# Rcrd_Brkr.net
KiCad netlist of a schematic drawn in Altium Designer
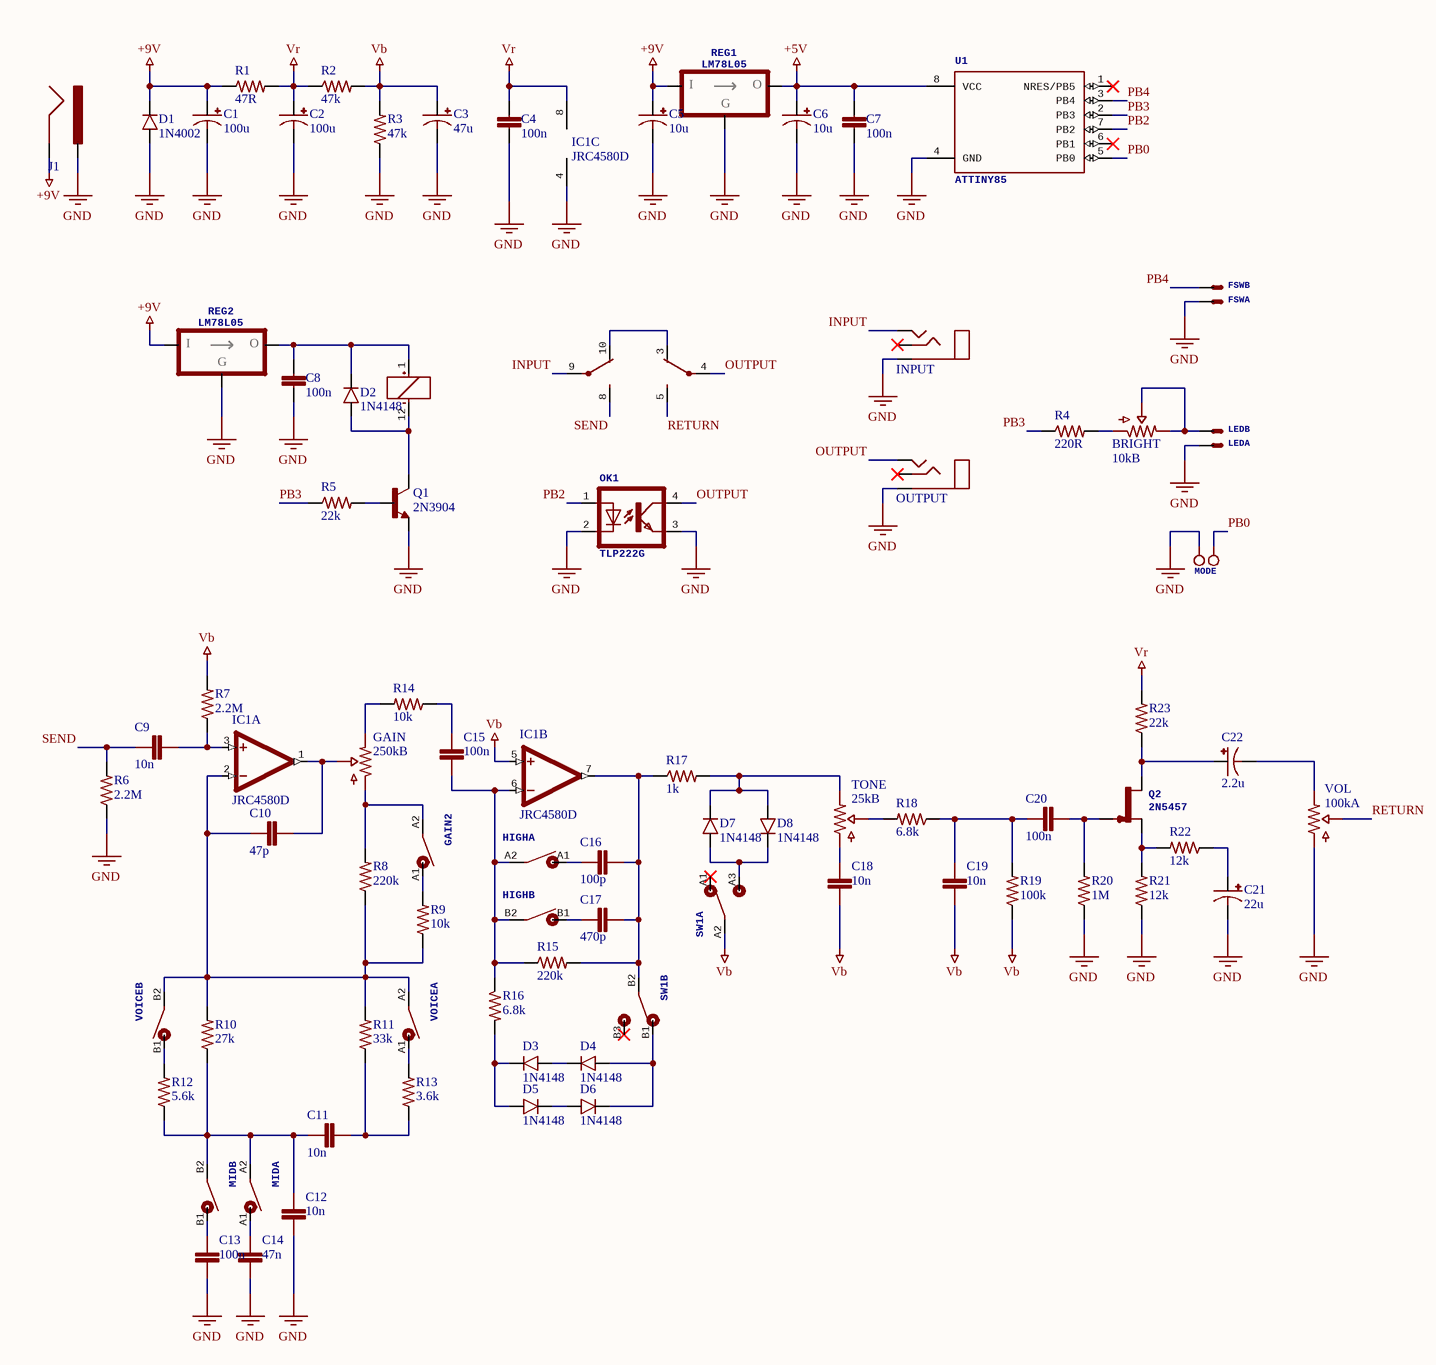
[diagram p0: Rcrd Brkr.SchDoc]

(export (version "E")
  (design (tool "Eeschema 10.0.6"))
  (components
    (comp (ref "BRIGHT")
      (value "10kB")
      (footprint "BOURNS_3362P")
      (description "10k Lin 3362P trimmer")
      (libsource (lib "Pedals") (part "TRIM_10kB_3362P"))
    )
    (comp (ref "C1")
      (value "100u")
      (footprint "ELEC_050_020")
      (description "100u 16V electrolytic capacitor")
      (libsource (lib "Pedals") (part "C_ELEC_100u_16V"))
    )
    (comp (ref "C2")
      (value "100u")
      (footprint "ELEC_050_020")
      (description "100u 16V electrolytic capacitor")
      (libsource (lib "Pedals") (part "C_ELEC_100u_16V"))
    )
    (comp (ref "C3")
      (value "47u")
      (footprint "ELEC_050_020")
      (description "47u 25V electrolytic capacitor")
      (libsource (lib "Pedals") (part "ELEC_47u_25V"))
    )
    (comp (ref "C4")
      (value "100n")
      (footprint "CER_050")
      (description "100n MLCC X7R radial capacitor")
      (libsource (lib "") (part "CER_100n_1"))
    )
    (comp (ref "C5")
      (value "10u")
      (footprint "ELEC_040_020")
      (description "10u 50V electrolytic capacitor")
      (libsource (lib "Pedals") (part "ELEC_10u_50V"))
    )
    (comp (ref "C6")
      (value "10u")
      (footprint "ELEC_040_020")
      (description "10u 50V electrolytic capacitor")
      (libsource (lib "Pedals") (part "ELEC_10u_50V"))
    )
    (comp (ref "C7")
      (value "100n")
      (footprint "CER_050")
      (description "100n MLCC X7R radial capacitor")
      (libsource (lib "Pedals") (part "CER_100n"))
    )
    (comp (ref "C8")
      (value "100n")
      (footprint "CER_050")
      (description "100n MLCC X7R radial capacitor")
      (libsource (lib "") (part "CER_100n_1"))
    )
    (comp (ref "C9")
      (value "10n")
      (footprint "FILMBOX_SMALL")
      (description "10n 100V polyester film box capacitor")
      (libsource (lib "") (part "FILMBOX_10n_2"))
    )
    (comp (ref "C10")
      (value "47p")
      (footprint "CER_050")
      (description "47p MLCC X7R radial capacitor")
      (libsource (lib "Pedals") (part "C_CER_47p"))
    )
    (comp (ref "C11")
      (value "10n")
      (footprint "FILMBOX_SMALL")
      (description "10n 100V polyester film box capacitor")
      (libsource (lib "") (part "FILMBOX_10n_2"))
    )
    (comp (ref "C12")
      (value "10n")
      (footprint "FILMBOX_SMALL")
      (description "10n 100V polyester film box capacitor")
      (libsource (lib "Pedals") (part "FILMBOX_10n"))
    )
    (comp (ref "C13")
      (value "100n")
      (footprint "FILMBOX_SMALL")
      (description "100n 100V polyester film box capacitor")
      (libsource (lib "") (part "C_FILMBOX_100n_1"))
    )
    (comp (ref "C14")
      (value "47n")
      (footprint "FILMBOX_SMALL")
      (description "47n 100V polyester film box capacitor")
      (libsource (lib "Pedals") (part "C_FILMBOX_47n"))
    )
    (comp (ref "C15")
      (value "100n")
      (footprint "FILMBOX_SMALL")
      (description "100n 100V polyester film box capacitor")
      (libsource (lib "Pedals") (part "FILMBOX_100n"))
    )
    (comp (ref "C16")
      (value "100p")
      (footprint "CER_050")
      (description "100p MLCC X7R radial capacitor")
      (libsource (lib "Pedals") (part "C_CER_100p"))
    )
    (comp (ref "C17")
      (value "470p")
      (footprint "CER_050")
      (description "470p MLCC X7R radial capacitor")
      (libsource (lib "Pedals") (part "C_CER_470p"))
    )
    (comp (ref "C18")
      (value "10n")
      (footprint "FILMBOX_SMALL")
      (description "10n 100V polyester film box capacitor")
      (libsource (lib "Pedals") (part "FILMBOX_10n"))
    )
    (comp (ref "C19")
      (value "10n")
      (footprint "FILMBOX_SMALL")
      (description "10n 100V polyester film box capacitor")
      (libsource (lib "") (part "FILMBOX_10n_1"))
    )
    (comp (ref "C20")
      (value "100n")
      (footprint "FILMBOX_SMALL")
      (description "100n 100V polyester film box capacitor")
      (libsource (lib "Pedals") (part "C_FILMBOX_100n"))
    )
    (comp (ref "C21")
      (value "22u")
      (footprint "ELEC_LESR_050_020")
      (description "22u 50V Low ESR ectrolytic capacitor")
      (libsource (lib "Pedals") (part "C_ELEC_LESR_22u_50V"))
    )
    (comp (ref "C22")
      (value "2.2u")
      (footprint "ELEC_LESR_050_020")
      (description "2.2u 50V Low ESR ectrolytic capacitor")
      (libsource (lib "Pedals") (part "C_ELEC_LESR_2.2u_50V"))
    )
    (comp (ref "D1") (value "1N4002") (footprint "DO41_2") (libsource (lib "Pedals") (part "1N4002")))
    (comp (ref "D2") (value "1N4148") (footprint "DO35_2") (libsource (lib "Pedals") (part "1N4148")))
    (comp (ref "D3") (value "1N4148") (footprint "DO35_2") (libsource (lib "Pedals") (part "1N4148")))
    (comp (ref "D4") (value "1N4148") (footprint "DO35_2") (libsource (lib "Pedals") (part "1N4148")))
    (comp (ref "D5") (value "1N4148") (footprint "DO35_2") (libsource (lib "Pedals") (part "1N4148")))
    (comp (ref "D6") (value "1N4148") (footprint "DO35_2") (libsource (lib "Pedals") (part "1N4148")))
    (comp (ref "D7") (value "1N4148") (footprint "DO35_2") (libsource (lib "Pedals") (part "1N4148")))
    (comp (ref "D8") (value "1N4148") (footprint "DO35_2") (libsource (lib "Pedals") (part "1N4148")))
    (comp (ref "FSW")
      (value "~")
      (footprint "JST-XH-02")
      (description "2 Pins male XH header")
      (libsource (lib "Pedals") (part "JST-XH-02"))
    )
    (comp (ref "GAIN")
      (value "250kB")
      (footprint "ALPHA_16mm_BOTTOM")
      (description "250k Lin potentiometer round shaft")
      (libsource (lib "Pedals") (part "250kB_ALPHA_16mm"))
    )
    (comp (ref "GAIN2")
      (value "DIP")
      (footprint "DIP_1WAY")
      (description "DIP Switch 1 way")
      (libsource (lib "Pedals") (part "SW_DIP_1WAY"))
    )
    (comp (ref "HIGH")
      (value "DIP")
      (footprint "DIP_2WAY")
      (description "DIP Switch 2 way")
      (libsource (lib "Pedals") (part "SW_DIP_2WAY"))
    )
    (comp (ref "IC1") (value "JRC4580D") (footprint "DIL8") (libsource (lib "Pedals") (part "JRC4580D")))
    (comp (ref "INPUT")
      (value "~")
      (footprint "STEREO")
      (description "6.35mm stereo insulated socket jack PCB mounted")
      (libsource (lib "Pedals") (part "STEREO"))
    )
    (comp (ref "J1")
      (value "DC_JACK")
      (footprint "DC_JACK")
      (description "DC Power jack 2.1mm barrel")
      (libsource (lib "Pedals") (part "DC_JACK"))
    )
    (comp (ref "K1")
      (value "~")
      (footprint "NA5")
      (description "NA5W-K")
      (libsource (lib "") (part "NA5W-K_1"))
    )
    (comp (ref "LED")
      (value "~")
      (footprint "JST-XH-02")
      (description "2 Pins male XH header")
      (libsource (lib "Pedals") (part "JST-XH-02"))
    )
    (comp (ref "MID")
      (value "DIP")
      (footprint "DIP_2WAY")
      (description "DIP Switch 2 way")
      (libsource (lib "Pedals") (part "SW_DIP_2WAY"))
    )
    (comp (ref "MODE")
      (value "HEADER_2PINS")
      (footprint "HEADER_2PINS")
      (description "2 Pins male header")
      (libsource (lib "Pedals") (part "HEADER_2PINS"))
    )
    (comp (ref "OK1") (value "TLP222G") (footprint "DIL4") (libsource (lib "Pedals") (part "TLP222G")))
    (comp (ref "OUTPUT")
      (value "~")
      (footprint "STEREO")
      (description "6.35mm stereo insulated socket jack PCB mounted")
      (libsource (lib "Pedals") (part "STEREO"))
    )
    (comp (ref "Q1") (value "2N3904") (footprint "TO92") (libsource (lib "Pedals") (part "2N3904")))
    (comp (ref "Q2") (value "2N5457") (footprint "TO92") (libsource (lib "Pedals") (part "Q_2N5457")))
    (comp (ref "R1")
      (value "47R")
      (footprint "R_3_47R_025W")
      (description "47R metal film 1/4W Resistor")
      (libsource (lib "Pedals") (part "R_3_47R_025W"))
    )
    (comp (ref "R2")
      (value "47k")
      (footprint "R_3_47k_025W")
      (description "47k metal film 1/4W Resistor")
      (libsource (lib "Pedals") (part "R_3_47k_025W"))
    )
    (comp (ref "R3")
      (value "47k")
      (footprint "R_3_47k_025W")
      (description "47k metal film 1/4W Resistor")
      (libsource (lib "Pedals") (part "R_3_47k_025W"))
    )
    (comp (ref "R4")
      (value "220R")
      (footprint "R_3_220R_025W")
      (description "220R metal film 1/4W Resistor")
      (libsource (lib "Pedals") (part "R_3_220R_025W"))
    )
    (comp (ref "R5")
      (value "22k")
      (footprint "R_3_22k_025W")
      (description "22k metal film 1/4W Resistor")
      (libsource (lib "Pedals") (part "R_3_22k_025W"))
    )
    (comp (ref "R6")
      (value "2.2M")
      (footprint "R_3_2,2M_025W")
      (description "2.2M metal film 1/4W Resistor")
      (libsource (lib "Pedals") (part "R_3_2.2M_025W"))
    )
    (comp (ref "R7")
      (value "2.2M")
      (footprint "R_3_2,2M_025W")
      (description "2.2M metal film 1/4W Resistor")
      (libsource (lib "Pedals") (part "R_3_2.2M_025W"))
    )
    (comp (ref "R8")
      (value "220k")
      (footprint "R_3_220k_025W")
      (description "220k metal film 1/4W Resistor")
      (libsource (lib "Pedals") (part "R_3_220k_025W"))
    )
    (comp (ref "R9")
      (value "10k")
      (footprint "R_3_10k_025W")
      (description "10k metal film 1/4W Resistor")
      (libsource (lib "Pedals") (part "R_3_10k_025W"))
    )
    (comp (ref "R10")
      (value "27k")
      (footprint "R_3_27k_025W")
      (description "27k metal film 1/4W Resistor")
      (libsource (lib "Pedals") (part "R_3_27k_025W"))
    )
    (comp (ref "R11")
      (value "33k")
      (footprint "R_3_33k_025W")
      (description "33k metal film 1/4W Resistor")
      (libsource (lib "Pedals") (part "R_3_33k_025W"))
    )
    (comp (ref "R12")
      (value "5.6k")
      (footprint "R_3_5.6k_025W")
      (description "5.6k metal film 1/4W Resistor")
      (libsource (lib "Pedals") (part "R_3_5.6k_025W"))
    )
    (comp (ref "R13")
      (value "3.6k")
      (footprint "R_3_3.6k_025W")
      (description "3.6k metal film 1/4W Resistor")
      (libsource (lib "Pedals") (part "R_3_3.6k_025W"))
    )
    (comp (ref "R14")
      (value "10k")
      (footprint "R_3_10k_025W")
      (description "10k metal film 1/4W Resistor")
      (libsource (lib "Pedals") (part "R_3_10k_025W"))
    )
    (comp (ref "R15")
      (value "220k")
      (footprint "R_3_220k_025W")
      (description "220k metal film 1/4W Resistor")
      (libsource (lib "Pedals") (part "R_3_220k_025W"))
    )
    (comp (ref "R16")
      (value "6.8k")
      (footprint "R_3_6.8k_025W")
      (description "6.8k metal film 1/4W Resistor")
      (libsource (lib "Pedals") (part "R_3_6.8k_025W"))
    )
    (comp (ref "R17")
      (value "1k")
      (footprint "R_3_1k_025W")
      (description "1k metal film 1/4W Resistor")
      (libsource (lib "Pedals") (part "R_3_1k_025W"))
    )
    (comp (ref "R18")
      (value "6.8k")
      (footprint "R_3_6.8k_025W")
      (description "6.8k metal film 1/4W Resistor")
      (libsource (lib "Pedals") (part "R_3_6.8k_025W"))
    )
    (comp (ref "R19")
      (value "100k")
      (footprint "R_3_100k_025W")
      (description "100k metal film 1/4W Resistor")
      (libsource (lib "Pedals") (part "R_3_100k_025W"))
    )
    (comp (ref "R20")
      (value "1M")
      (footprint "R_3_1M_025W")
      (description "1M metal film 1/4W Resistor")
      (libsource (lib "Pedals") (part "R_3_1M_025W"))
    )
    (comp (ref "R21")
      (value "12k")
      (footprint "R_3_12k_025W")
      (description "12k metal film 1/4W Resistor")
      (libsource (lib "Pedals") (part "R_3_12k_025W"))
    )
    (comp (ref "R22")
      (value "12k")
      (footprint "R_3_12k_025W")
      (description "12k metal film 1/4W Resistor")
      (libsource (lib "Pedals") (part "R_3_12k_025W"))
    )
    (comp (ref "R23")
      (value "22k")
      (footprint "R_3_22k_025W")
      (description "22k metal film 1/4W Resistor")
      (libsource (lib "Pedals") (part "R_3_22k_025W"))
    )
    (comp (ref "REG1")
      (value "LM78L05")
      (footprint "TO92")
      (description "78L05")
      (libsource (lib "Pedals") (part "LM78L05"))
    )
    (comp (ref "REG2")
      (value "LM78L05")
      (footprint "TO92")
      (description "78L05")
      (libsource (lib "Pedals") (part "LM78L05"))
    )
    (comp (ref "SW1")
      (value "DPDT")
      (footprint "DPDT")
      (description "DPDT toggle switch ON/OFF/ON")
      (libsource (lib "") (part "DPDT_ON-OFF-ON_1"))
    )
    (comp (ref "TONE")
      (value "25kB")
      (footprint "ALPHA_16mm_BOTTOM")
      (description "25k Lin potentiometer round shaft")
      (libsource (lib "Pedals") (part "25kB_ALPHA_16mm"))
    )
    (comp (ref "U1")
      (value "ATTINY85")
      (footprint "DIP8")
      (description "ATTINY85-20PU")
      (libsource (lib "Pedals") (part "ATTINY85"))
    )
    (comp (ref "VOICE")
      (value "DIP")
      (footprint "DIP_2WAY")
      (description "DIP Switch 2 way")
      (libsource (lib "") (part "SW_DIP_2WAY_2"))
    )
    (comp (ref "VOL")
      (value "100kA")
      (footprint "ALPHA_16mm_BOTTOM")
      (description "100k Log potentiometer round shaft")
      (libsource (lib "Pedals") (part "100kA_ALPHA_16mm"))
    )
  )
  (nets
    (net (code "1") (name "+5V") (class "Default")
      (node (ref "C6") (pin "+") (pinfunction "+_+") (pintype "passive"))
      (node (ref "C7") (pin "2") (pinfunction "2_2") (pintype "passive"))
      (node (ref "REG1") (pin "3") (pinfunction "VO_3") (pintype "power_in"))
      (node (ref "U1") (pin "8") (pinfunction "VCC_8") (pintype "power_in"))
    )
    (net (code "2") (name "+9V") (class "Default")
      (node (ref "C1") (pin "+") (pinfunction "+_+") (pintype "passive"))
      (node (ref "C5") (pin "+") (pinfunction "+_+") (pintype "passive"))
      (node (ref "D1") (pin "C") (pinfunction "C_C") (pintype "passive"))
      (node (ref "J1") (pin "GND") (pinfunction "GND_GND") (pintype "passive"))
      (node (ref "R1") (pin "1") (pinfunction "1_1") (pintype "passive"))
      (node (ref "REG1") (pin "1") (pinfunction "VI_1") (pintype "power_in"))
      (node (ref "REG2") (pin "1") (pinfunction "VI_1") (pintype "power_in"))
    )
    (net (code "3") (name "/INPUT") (class "Default")
      (node (ref "INPUT") (pin "T") (pinfunction "T_T") (pintype "passive"))
      (node (ref "K1") (pin "9") (pinfunction "P_9") (pintype "passive"))
    )
    (net (code "4") (name "/OUTPUT") (class "Default")
      (node (ref "K1") (pin "4") (pinfunction "P_4") (pintype "passive"))
      (node (ref "OK1") (pin "4") (pinfunction "COL_4") (pintype "passive"))
      (node (ref "OUTPUT") (pin "T") (pinfunction "T_T") (pintype "passive"))
    )
    (net (code "5") (name "/PB0") (class "Default")
      (node (ref "MODE") (pin "2") (pinfunction "2_2") (pintype "passive"))
      (node (ref "U1") (pin "5") (pinfunction "PB0_5") (pintype "bidirectional"))
    )
    (net (code "6") (name "/PB2") (class "Default")
      (node (ref "OK1") (pin "1") (pinfunction "A_1") (pintype "passive"))
      (node (ref "U1") (pin "7") (pinfunction "PB2_7") (pintype "bidirectional"))
    )
    (net (code "7") (name "/PB3") (class "Default")
      (node (ref "R4") (pin "1") (pinfunction "1_1") (pintype "passive"))
      (node (ref "R5") (pin "1") (pinfunction "1_1") (pintype "passive"))
      (node (ref "U1") (pin "2") (pinfunction "PB3_2") (pintype "bidirectional"))
    )
    (net (code "8") (name "/PB4") (class "Default")
      (node (ref "FSW") (pin "1") (pinfunction "S_1") (pintype "passive"))
      (node (ref "U1") (pin "3") (pinfunction "PB4_3") (pintype "bidirectional"))
    )
    (net (code "9") (name "/RETURN") (class "Default")
      (node (ref "K1") (pin "5") (pinfunction "S_5") (pintype "passive"))
      (node (ref "VOL") (pin "2") (pinfunction "2_2") (pintype "passive"))
    )
    (net (code "10") (name "/SEND") (class "Default")
      (node (ref "C9") (pin "2") (pinfunction "2_2") (pintype "passive"))
      (node (ref "K1") (pin "8") (pinfunction "S_8") (pintype "passive"))
      (node (ref "R6") (pin "2") (pinfunction "2_2") (pintype "passive"))
    )
    (net (code "11") (name "GND") (class "Default")
      (node (ref "C1") (pin "-") (pinfunction "-_-") (pintype "passive"))
      (node (ref "C12") (pin "2") (pinfunction "2_2") (pintype "passive"))
      (node (ref "C13") (pin "2") (pinfunction "2_2") (pintype "passive"))
      (node (ref "C14") (pin "2") (pinfunction "2_2") (pintype "passive"))
      (node (ref "C2") (pin "-") (pinfunction "-_-") (pintype "passive"))
      (node (ref "C21") (pin "-") (pinfunction "-_-") (pintype "passive"))
      (node (ref "C3") (pin "-") (pinfunction "-_-") (pintype "passive"))
      (node (ref "C4") (pin "2") (pinfunction "2_2") (pintype "passive"))
      (node (ref "C5") (pin "-") (pinfunction "-_-") (pintype "passive"))
      (node (ref "C6") (pin "-") (pinfunction "-_-") (pintype "passive"))
      (node (ref "C7") (pin "1") (pinfunction "1_1") (pintype "passive"))
      (node (ref "C8") (pin "2") (pinfunction "2_2") (pintype "passive"))
      (node (ref "D1") (pin "A") (pinfunction "A_A") (pintype "passive"))
      (node (ref "FSW") (pin "2") (pinfunction "S_2") (pintype "passive"))
      (node (ref "IC1") (pin "4") (pinfunction "V-_4") (pintype "power_in"))
      (node (ref "INPUT") (pin "S") (pinfunction "S_S") (pintype "passive"))
      (node (ref "J1") (pin "PWR") (pinfunction "PWR_PWR") (pintype "passive"))
      (node (ref "LED") (pin "2") (pinfunction "S_2") (pintype "passive"))
      (node (ref "MODE") (pin "1") (pinfunction "1_1") (pintype "passive"))
      (node (ref "OK1") (pin "2") (pinfunction "C_2") (pintype "passive"))
      (node (ref "OK1") (pin "3") (pinfunction "EMIT_3") (pintype "passive"))
      (node (ref "OUTPUT") (pin "S") (pinfunction "S_S") (pintype "passive"))
      (node (ref "Q1") (pin "3") (pinfunction "E_3") (pintype "passive"))
      (node (ref "R20") (pin "1") (pinfunction "1_1") (pintype "passive"))
      (node (ref "R21") (pin "1") (pinfunction "1_1") (pintype "passive"))
      (node (ref "R3") (pin "1") (pinfunction "1_1") (pintype "passive"))
      (node (ref "R6") (pin "1") (pinfunction "1_1") (pintype "passive"))
      (node (ref "REG1") (pin "2") (pinfunction "GND_2") (pintype "power_in"))
      (node (ref "REG2") (pin "2") (pinfunction "GND_2") (pintype "power_in"))
      (node (ref "U1") (pin "4") (pinfunction "GND_4") (pintype "power_in"))
      (node (ref "VOL") (pin "1") (pinfunction "1_1") (pintype "passive"))
    )
    (net (code "12") (name "Net-(BRIGHT-Pad1)") (class "Default")
      (node (ref "BRIGHT") (pin "1") (pinfunction "1_1") (pintype "passive"))
      (node (ref "R4") (pin "2") (pinfunction "2_2") (pintype "passive"))
    )
    (net (code "13") (name "Net-(C11-Pad1)") (class "Default")
      (node (ref "C11") (pin "1") (pinfunction "1_1") (pintype "passive"))
      (node (ref "R11") (pin "1") (pinfunction "1_1") (pintype "passive"))
      (node (ref "R13") (pin "1") (pinfunction "1_1") (pintype "passive"))
    )
    (net (code "14") (name "Net-(C15-Pad1)") (class "Default")
      (node (ref "C15") (pin "1") (pinfunction "1_1") (pintype "passive"))
      (node (ref "R14") (pin "1") (pinfunction "1_1") (pintype "passive"))
    )
    (net (code "15") (name "Net-(C18-Pad1)") (class "Default")
      (node (ref "C18") (pin "1") (pinfunction "1_1") (pintype "passive"))
      (node (ref "TONE") (pin "1") (pinfunction "1_1") (pintype "passive"))
    )
    (net (code "16") (name "Net-(C19-Pad2)") (class "Default")
      (node (ref "C19") (pin "2") (pinfunction "2_2") (pintype "passive"))
      (node (ref "C20") (pin "2") (pinfunction "2_2") (pintype "passive"))
      (node (ref "R18") (pin "1") (pinfunction "1_1") (pintype "passive"))
      (node (ref "R19") (pin "2") (pinfunction "2_2") (pintype "passive"))
    )
    (net (code "17") (name "Net-(C21-Pad+)") (class "Default")
      (node (ref "C21") (pin "+") (pinfunction "+_+") (pintype "passive"))
      (node (ref "R22") (pin "1") (pinfunction "1_1") (pintype "passive"))
    )
    (net (code "18") (name "Net-(C22-Pad-)") (class "Default")
      (node (ref "C22") (pin "-") (pinfunction "-_-") (pintype "passive"))
      (node (ref "VOL") (pin "3") (pinfunction "3_3") (pintype "passive"))
    )
    (net (code "19") (name "Net-(D3-PadA)") (class "Default")
      (node (ref "D3") (pin "A") (pinfunction "A_A") (pintype "passive"))
      (node (ref "D4") (pin "C") (pinfunction "C_C") (pintype "passive"))
    )
    (net (code "20") (name "Net-(D3-PadC)") (class "Default")
      (node (ref "D3") (pin "C") (pinfunction "C_C") (pintype "passive"))
      (node (ref "D5") (pin "A") (pinfunction "A_A") (pintype "passive"))
      (node (ref "R16") (pin "2") (pinfunction "2_2") (pintype "passive"))
    )
    (net (code "21") (name "Net-(D5-PadC)") (class "Default")
      (node (ref "D5") (pin "C") (pinfunction "C_C") (pintype "passive"))
      (node (ref "D6") (pin "A") (pinfunction "A_A") (pintype "passive"))
    )
    (net (code "22") (name "Net-(D7-PadC)") (class "Default")
      (node (ref "D7") (pin "C") (pinfunction "C_C") (pintype "passive"))
      (node (ref "D8") (pin "A") (pinfunction "A_A") (pintype "passive"))
      (node (ref "R17") (pin "2") (pinfunction "2_2") (pintype "passive"))
      (node (ref "TONE") (pin "3") (pinfunction "3_3") (pintype "passive"))
    )
    (net (code "23") (name "Net-(GAIN-Pad3)") (class "Default")
      (node (ref "GAIN") (pin "3") (pinfunction "3_3") (pintype "passive"))
      (node (ref "R14") (pin "2") (pinfunction "2_2") (pintype "passive"))
    )
    (net (code "24") (name "Net-(GAIN2-1)") (class "Default")
      (node (ref "GAIN2") (pin "A1") (pinfunction "1_A1") (pintype "passive"))
      (node (ref "R9") (pin "2") (pinfunction "2_2") (pintype "passive"))
    )
    (net (code "25") (name "Net-(GAIN2-2)") (class "Default")
      (node (ref "GAIN") (pin "1") (pinfunction "1_1") (pintype "passive"))
      (node (ref "GAIN2") (pin "A2") (pinfunction "2_A2") (pintype "passive"))
      (node (ref "R8") (pin "2") (pinfunction "2_2") (pintype "passive"))
    )
    (net (code "26") (name "Net-(HIGHA-1)") (class "Default")
      (node (ref "C16") (pin "2") (pinfunction "2_2") (pintype "passive"))
      (node (ref "HIGH") (pin "A1") (pinfunction "1_A1") (pintype "passive"))
    )
    (net (code "27") (name "Net-(HIGHA-2)") (class "Default")
      (node (ref "C15") (pin "2") (pinfunction "2_2") (pintype "passive"))
      (node (ref "HIGH") (pin "A2") (pinfunction "2_A2") (pintype "passive"))
      (node (ref "HIGH") (pin "B2") (pinfunction "2_B2") (pintype "passive"))
      (node (ref "IC1") (pin "6") (pinfunction "-IN_6") (pintype "input"))
      (node (ref "R15") (pin "1") (pinfunction "1_1") (pintype "passive"))
      (node (ref "R16") (pin "1") (pinfunction "1_1") (pintype "passive"))
    )
    (net (code "28") (name "Net-(HIGHB-1)") (class "Default")
      (node (ref "C17") (pin "2") (pinfunction "2_2") (pintype "passive"))
      (node (ref "HIGH") (pin "B1") (pinfunction "1_B1") (pintype "passive"))
    )
    (net (code "29") (name "Net-(IC1A-+IN)") (class "Default")
      (node (ref "C9") (pin "1") (pinfunction "1_1") (pintype "passive"))
      (node (ref "IC1") (pin "3") (pinfunction "+IN_3") (pintype "input"))
      (node (ref "R7") (pin "1") (pinfunction "1_1") (pintype "passive"))
    )
    (net (code "30") (name "Net-(IC1A--IN)") (class "Default")
      (node (ref "C10") (pin "2") (pinfunction "2_2") (pintype "passive"))
      (node (ref "IC1") (pin "2") (pinfunction "-IN_2") (pintype "input"))
      (node (ref "R10") (pin "2") (pinfunction "2_2") (pintype "passive"))
      (node (ref "R11") (pin "2") (pinfunction "2_2") (pintype "passive"))
      (node (ref "R8") (pin "1") (pinfunction "1_1") (pintype "passive"))
      (node (ref "R9") (pin "1") (pinfunction "1_1") (pintype "passive"))
      (node (ref "VOICE") (pin "A2") (pinfunction "2_A2") (pintype "passive"))
      (node (ref "VOICE") (pin "B2") (pinfunction "2_B2") (pintype "passive"))
    )
    (net (code "31") (name "Net-(IC1A-OUT)") (class "Default")
      (node (ref "C10") (pin "1") (pinfunction "1_1") (pintype "passive"))
      (node (ref "GAIN") (pin "2") (pinfunction "2_2") (pintype "passive"))
      (node (ref "IC1") (pin "1") (pinfunction "OUT_1") (pintype "output"))
    )
    (net (code "32") (name "Net-(IC1B-OUT)") (class "Default")
      (node (ref "C16") (pin "1") (pinfunction "1_1") (pintype "passive"))
      (node (ref "C17") (pin "1") (pinfunction "1_1") (pintype "passive"))
      (node (ref "IC1") (pin "7") (pinfunction "OUT_7") (pintype "output"))
      (node (ref "R15") (pin "2") (pinfunction "2_2") (pintype "passive"))
      (node (ref "R17") (pin "1") (pinfunction "1_1") (pintype "passive"))
      (node (ref "SW1") (pin "B2") (pinfunction "2_B2") (pintype "passive"))
    )
    (net (code "33") (name "Net-(K1A-+)") (class "Default")
      (node (ref "C8") (pin "1") (pinfunction "1_1") (pintype "passive"))
      (node (ref "D2") (pin "C") (pinfunction "C_C") (pintype "passive"))
      (node (ref "K1") (pin "1") (pinfunction "+_1") (pintype "passive"))
      (node (ref "REG2") (pin "3") (pinfunction "VO_3") (pintype "power_in"))
    )
    (net (code "34") (name "Net-(K1A--)") (class "Default")
      (node (ref "D2") (pin "A") (pinfunction "A_A") (pintype "passive"))
      (node (ref "K1") (pin "12") (pinfunction "-_12") (pintype "passive"))
      (node (ref "Q1") (pin "1") (pinfunction "C_1") (pintype "passive"))
    )
    (net (code "35") (name "Net-(K1B-O)") (class "Default")
      (node (ref "K1") (pin "10") (pinfunction "O_10") (pintype "passive"))
      (node (ref "K1") (pin "3") (pinfunction "O_3") (pintype "passive"))
    )
    (net (code "36") (name "Net-(LEDB-S)") (class "Default")
      (node (ref "BRIGHT") (pin "2") (pinfunction "2_2") (pintype "passive"))
      (node (ref "BRIGHT") (pin "3") (pinfunction "3_3") (pintype "passive"))
      (node (ref "LED") (pin "1") (pinfunction "S_1") (pintype "passive"))
    )
    (net (code "37") (name "Net-(MIDA-1)") (class "Default")
      (node (ref "C14") (pin "1") (pinfunction "1_1") (pintype "passive"))
      (node (ref "MID") (pin "A1") (pinfunction "1_A1") (pintype "passive"))
    )
    (net (code "38") (name "Net-(MIDA-2)") (class "Default")
      (node (ref "C11") (pin "2") (pinfunction "2_2") (pintype "passive"))
      (node (ref "C12") (pin "1") (pinfunction "1_1") (pintype "passive"))
      (node (ref "MID") (pin "A2") (pinfunction "2_A2") (pintype "passive"))
      (node (ref "MID") (pin "B2") (pinfunction "2_B2") (pintype "passive"))
      (node (ref "R10") (pin "1") (pinfunction "1_1") (pintype "passive"))
      (node (ref "R12") (pin "1") (pinfunction "1_1") (pintype "passive"))
    )
    (net (code "39") (name "Net-(MIDB-1)") (class "Default")
      (node (ref "C13") (pin "1") (pinfunction "1_1") (pintype "passive"))
      (node (ref "MID") (pin "B1") (pinfunction "1_B1") (pintype "passive"))
    )
    (net (code "40") (name "Net-(Q1-B)") (class "Default")
      (node (ref "Q1") (pin "2") (pinfunction "B_2") (pintype "passive"))
      (node (ref "R5") (pin "2") (pinfunction "2_2") (pintype "passive"))
    )
    (net (code "41") (name "Net-(Q2-D)") (class "Default")
      (node (ref "C22") (pin "+") (pinfunction "+_+") (pintype "passive"))
      (node (ref "Q2") (pin "3") (pinfunction "D_3") (pintype "passive"))
      (node (ref "R23") (pin "1") (pinfunction "1_1") (pintype "passive"))
    )
    (net (code "42") (name "Net-(Q2-G)") (class "Default")
      (node (ref "C20") (pin "1") (pinfunction "1_1") (pintype "passive"))
      (node (ref "Q2") (pin "1") (pinfunction "G_1") (pintype "passive"))
      (node (ref "R20") (pin "2") (pinfunction "2_2") (pintype "passive"))
    )
    (net (code "43") (name "Net-(Q2-S)") (class "Default")
      (node (ref "Q2") (pin "2") (pinfunction "S_2") (pintype "passive"))
      (node (ref "R21") (pin "2") (pinfunction "2_2") (pintype "passive"))
      (node (ref "R22") (pin "2") (pinfunction "2_2") (pintype "passive"))
    )
    (net (code "44") (name "Net-(R18-Pad2)") (class "Default")
      (node (ref "R18") (pin "2") (pinfunction "2_2") (pintype "passive"))
      (node (ref "TONE") (pin "2") (pinfunction "2_2") (pintype "passive"))
    )
    (net (code "45") (name "Net-(SW1A-3)") (class "Default")
      (node (ref "D7") (pin "A") (pinfunction "A_A") (pintype "passive"))
      (node (ref "D8") (pin "C") (pinfunction "C_C") (pintype "passive"))
      (node (ref "SW1") (pin "A3") (pinfunction "3_A3") (pintype "passive"))
    )
    (net (code "46") (name "Net-(SW1B-1)") (class "Default")
      (node (ref "D4") (pin "A") (pinfunction "A_A") (pintype "passive"))
      (node (ref "D6") (pin "C") (pinfunction "C_C") (pintype "passive"))
      (node (ref "SW1") (pin "B1") (pinfunction "1_B1") (pintype "passive"))
    )
    (net (code "47") (name "Net-(VOICEA-1)") (class "Default")
      (node (ref "R13") (pin "2") (pinfunction "2_2") (pintype "passive"))
      (node (ref "VOICE") (pin "A1") (pinfunction "1_A1") (pintype "passive"))
    )
    (net (code "48") (name "Net-(VOICEB-1)") (class "Default")
      (node (ref "R12") (pin "2") (pinfunction "2_2") (pintype "passive"))
      (node (ref "VOICE") (pin "B1") (pinfunction "1_B1") (pintype "passive"))
    )
    (net (code "49") (name "Vb") (class "Default")
      (node (ref "C18") (pin "2") (pinfunction "2_2") (pintype "passive"))
      (node (ref "C19") (pin "1") (pinfunction "1_1") (pintype "passive"))
      (node (ref "C3") (pin "+") (pinfunction "+_+") (pintype "passive"))
      (node (ref "IC1") (pin "5") (pinfunction "+IN_5") (pintype "input"))
      (node (ref "R19") (pin "1") (pinfunction "1_1") (pintype "passive"))
      (node (ref "R2") (pin "2") (pinfunction "2_2") (pintype "passive"))
      (node (ref "R3") (pin "2") (pinfunction "2_2") (pintype "passive"))
      (node (ref "R7") (pin "2") (pinfunction "2_2") (pintype "passive"))
      (node (ref "SW1") (pin "A2") (pinfunction "2_A2") (pintype "passive"))
    )
    (net (code "50") (name "Vr") (class "Default")
      (node (ref "C2") (pin "+") (pinfunction "+_+") (pintype "passive"))
      (node (ref "C4") (pin "1") (pinfunction "1_1") (pintype "passive"))
      (node (ref "IC1") (pin "8") (pinfunction "V+_8") (pintype "power_in"))
      (node (ref "R1") (pin "2") (pinfunction "2_2") (pintype "passive"))
      (node (ref "R2") (pin "1") (pinfunction "1_1") (pintype "passive"))
      (node (ref "R23") (pin "2") (pinfunction "2_2") (pintype "passive"))
    )
    (net (code "51") (name "unconnected-(INPUT-PadR)") (class "Default")
      (node (ref "INPUT") (pin "R") (pinfunction "R_R") (pintype "passive+no_connect"))
    )
    (net (code "52") (name "unconnected-(OUTPUT-PadR)") (class "Default")
      (node (ref "OUTPUT") (pin "R") (pinfunction "R_R") (pintype "passive+no_connect"))
    )
    (net (code "53") (name "unconnected-(SW1A-1-PadA1)") (class "Default")
      (node (ref "SW1") (pin "A1") (pinfunction "1_A1") (pintype "passive+no_connect"))
    )
    (net (code "54") (name "unconnected-(SW1B-3-PadB3)") (class "Default")
      (node (ref "SW1") (pin "B3") (pinfunction "3_B3") (pintype "passive+no_connect"))
    )
    (net (code "55") (name "unconnected-(U1-NRES{slash}PB5-Pad1)") (class "Default")
      (node (ref "U1") (pin "1") (pinfunction "NRES/PB5_1") (pintype "bidirectional+no_connect"))
    )
    (net (code "56") (name "unconnected-(U1-PB1-Pad6)") (class "Default")
      (node (ref "U1") (pin "6") (pinfunction "PB1_6") (pintype "bidirectional+no_connect"))
    )
  )
)
